# ConnectorPMOD.net
KiCad netlist of a schematic drawn in Altium Designer
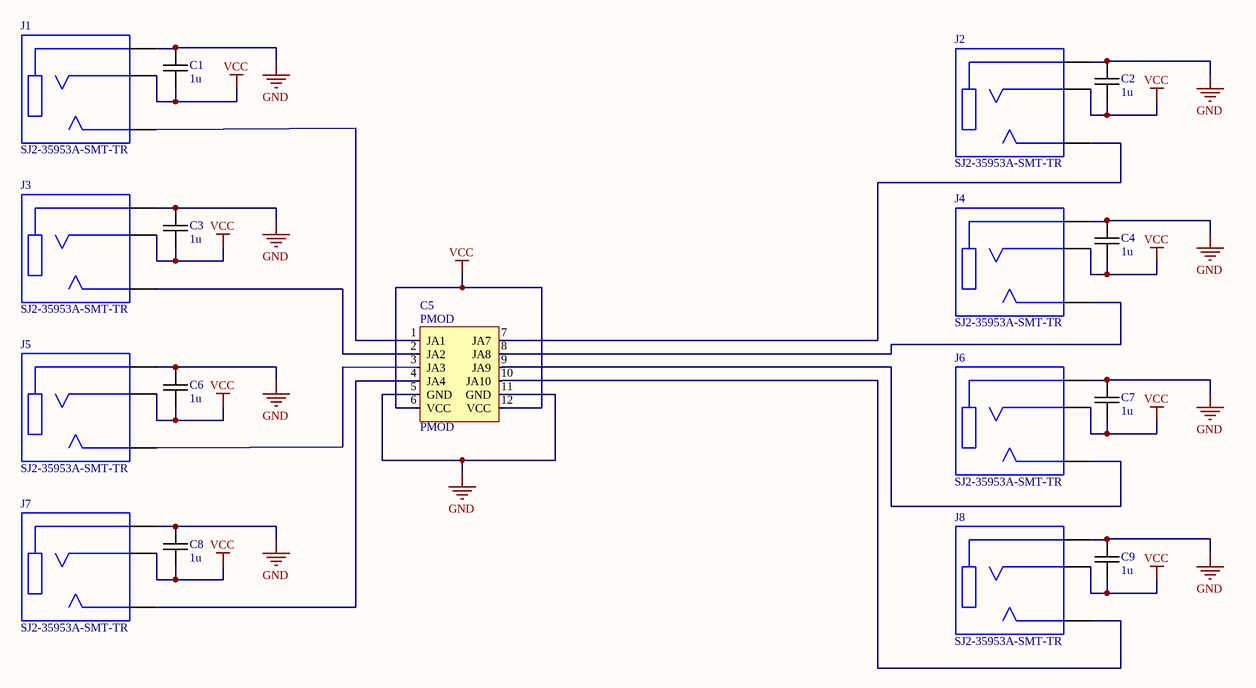
[diagram p0: ConnectorPMOD.SchDoc]

(export (version "E")
  (design (tool "Eeschema 10.0.6"))
  (components
    (comp (ref "C1")
      (value "1u")
      (footprint "0805C-GENERIC")
      (description "GENERIC CAPACITOR NON POLARISED0603")
      (libsource (lib "vh_altium_library") (part "C0805-GENERIC"))
    )
    (comp (ref "C2")
      (value "1u")
      (footprint "0805C-GENERIC")
      (description "GENERIC CAPACITOR NON POLARISED0603")
      (libsource (lib "vh_altium_library") (part "C0805-GENERIC"))
    )
    (comp (ref "C3")
      (value "1u")
      (footprint "0805C-GENERIC")
      (description "GENERIC CAPACITOR NON POLARISED0603")
      (libsource (lib "vh_altium_library") (part "C0805-GENERIC"))
    )
    (comp (ref "C4")
      (value "1u")
      (footprint "0805C-GENERIC")
      (description "GENERIC CAPACITOR NON POLARISED0603")
      (libsource (lib "vh_altium_library") (part "C0805-GENERIC"))
    )
    (comp (ref "C5") (value "PMOD") (footprint "PMOD") (libsource (lib "PMOD") (part "PMOD")))
    (comp (ref "C6")
      (value "1u")
      (footprint "0805C-GENERIC")
      (description "GENERIC CAPACITOR NON POLARISED0603")
      (libsource (lib "vh_altium_library") (part "C0805-GENERIC"))
    )
    (comp (ref "C7")
      (value "1u")
      (footprint "0805C-GENERIC")
      (description "GENERIC CAPACITOR NON POLARISED0603")
      (libsource (lib "vh_altium_library") (part "C0805-GENERIC"))
    )
    (comp (ref "C8")
      (value "1u")
      (footprint "0805C-GENERIC")
      (description "GENERIC CAPACITOR NON POLARISED0603")
      (libsource (lib "vh_altium_library") (part "C0805-GENERIC"))
    )
    (comp (ref "C9")
      (value "1u")
      (footprint "0805C-GENERIC")
      (description "GENERIC CAPACITOR NON POLARISED0603")
      (libsource (lib "vh_altium_library") (part "C0805-GENERIC"))
    )
    (comp (ref "J1")
      (value "SJ2-35953A-SMT-TR")
      (footprint "CUI_SJ2-35953A-SMT-TR")
      (description "3.5 mm, Stereo, Right Angle, Surface Mount _SMT_, Audio Jack Connector")
      (fields (field (name "MF") "CUI Devices"))
      (libsource (lib "SJ2-35953A-SMT-TR") (part "SJ2-35953A-SMT-TR"))
    )
    (comp (ref "J2")
      (value "SJ2-35953A-SMT-TR")
      (footprint "CUI_SJ2-35953A-SMT-TR")
      (description "3.5 mm, Stereo, Right Angle, Surface Mount _SMT_, Audio Jack Connector")
      (fields (field (name "MF") "CUI Devices"))
      (libsource (lib "SJ2-35953A-SMT-TR") (part "SJ2-35953A-SMT-TR"))
    )
    (comp (ref "J3")
      (value "SJ2-35953A-SMT-TR")
      (footprint "CUI_SJ2-35953A-SMT-TR")
      (description "3.5 mm, Stereo, Right Angle, Surface Mount _SMT_, Audio Jack Connector")
      (fields (field (name "MF") "CUI Devices"))
      (libsource (lib "SJ2-35953A-SMT-TR") (part "SJ2-35953A-SMT-TR"))
    )
    (comp (ref "J4")
      (value "SJ2-35953A-SMT-TR")
      (footprint "CUI_SJ2-35953A-SMT-TR")
      (description "3.5 mm, Stereo, Right Angle, Surface Mount _SMT_, Audio Jack Connector")
      (fields (field (name "MF") "CUI Devices"))
      (libsource (lib "SJ2-35953A-SMT-TR") (part "SJ2-35953A-SMT-TR"))
    )
    (comp (ref "J5")
      (value "SJ2-35953A-SMT-TR")
      (footprint "CUI_SJ2-35953A-SMT-TR")
      (description "3.5 mm, Stereo, Right Angle, Surface Mount _SMT_, Audio Jack Connector")
      (fields (field (name "MF") "CUI Devices"))
      (libsource (lib "SJ2-35953A-SMT-TR") (part "SJ2-35953A-SMT-TR"))
    )
    (comp (ref "J6")
      (value "SJ2-35953A-SMT-TR")
      (footprint "CUI_SJ2-35953A-SMT-TR")
      (description "3.5 mm, Stereo, Right Angle, Surface Mount _SMT_, Audio Jack Connector")
      (fields (field (name "MF") "CUI Devices"))
      (libsource (lib "SJ2-35953A-SMT-TR") (part "SJ2-35953A-SMT-TR"))
    )
    (comp (ref "J7")
      (value "SJ2-35953A-SMT-TR")
      (footprint "CUI_SJ2-35953A-SMT-TR")
      (description "3.5 mm, Stereo, Right Angle, Surface Mount _SMT_, Audio Jack Connector")
      (fields (field (name "MF") "CUI Devices"))
      (libsource (lib "SJ2-35953A-SMT-TR") (part "SJ2-35953A-SMT-TR"))
    )
    (comp (ref "J8")
      (value "SJ2-35953A-SMT-TR")
      (footprint "CUI_SJ2-35953A-SMT-TR")
      (description "3.5 mm, Stereo, Right Angle, Surface Mount _SMT_, Audio Jack Connector")
      (fields (field (name "MF") "CUI Devices"))
      (libsource (lib "SJ2-35953A-SMT-TR") (part "SJ2-35953A-SMT-TR"))
    )
  )
  (nets
    (net (code "1") (name "GND") (class "Default")
      (node (ref "C1") (pin "1") (pintype "passive"))
      (node (ref "C2") (pin "1") (pintype "passive"))
      (node (ref "C3") (pin "1") (pintype "passive"))
      (node (ref "C4") (pin "1") (pintype "passive"))
      (node (ref "C5") (pin "11") (pinfunction "GND_11") (pintype "power_in"))
      (node (ref "C5") (pin "5") (pinfunction "GND_5") (pintype "power_in"))
      (node (ref "C6") (pin "1") (pintype "passive"))
      (node (ref "C7") (pin "1") (pintype "passive"))
      (node (ref "C8") (pin "1") (pintype "passive"))
      (node (ref "C9") (pin "1") (pintype "passive"))
      (node (ref "J1") (pin "1") (pinfunction "SLEEVE_1") (pintype "passive"))
      (node (ref "J2") (pin "1") (pinfunction "SLEEVE_1") (pintype "passive"))
      (node (ref "J3") (pin "1") (pinfunction "SLEEVE_1") (pintype "passive"))
      (node (ref "J4") (pin "1") (pinfunction "SLEEVE_1") (pintype "passive"))
      (node (ref "J5") (pin "1") (pinfunction "SLEEVE_1") (pintype "passive"))
      (node (ref "J6") (pin "1") (pinfunction "SLEEVE_1") (pintype "passive"))
      (node (ref "J7") (pin "1") (pinfunction "SLEEVE_1") (pintype "passive"))
      (node (ref "J8") (pin "1") (pinfunction "SLEEVE_1") (pintype "passive"))
    )
    (net (code "2") (name "Net-(C5-JA1)") (class "Default")
      (node (ref "C5") (pin "1") (pinfunction "JA1_1") (pintype "output"))
      (node (ref "J1") (pin "2") (pinfunction "TIP_2") (pintype "passive"))
    )
    (net (code "3") (name "Net-(C5-JA2)") (class "Default")
      (node (ref "C5") (pin "2") (pinfunction "JA2_2") (pintype "output"))
      (node (ref "J3") (pin "2") (pinfunction "TIP_2") (pintype "passive"))
    )
    (net (code "4") (name "Net-(C5-JA3)") (class "Default")
      (node (ref "C5") (pin "3") (pinfunction "JA3_3") (pintype "output"))
      (node (ref "J5") (pin "2") (pinfunction "TIP_2") (pintype "passive"))
    )
    (net (code "5") (name "Net-(C5-JA4)") (class "Default")
      (node (ref "C5") (pin "4") (pinfunction "JA4_4") (pintype "output"))
      (node (ref "J7") (pin "2") (pinfunction "TIP_2") (pintype "passive"))
    )
    (net (code "6") (name "Net-(C5-JA7)") (class "Default")
      (node (ref "C5") (pin "7") (pinfunction "JA7_7") (pintype "output"))
      (node (ref "J2") (pin "2") (pinfunction "TIP_2") (pintype "passive"))
    )
    (net (code "7") (name "Net-(C5-JA8)") (class "Default")
      (node (ref "C5") (pin "8") (pinfunction "JA8_8") (pintype "output"))
      (node (ref "J4") (pin "2") (pinfunction "TIP_2") (pintype "passive"))
    )
    (net (code "8") (name "Net-(C5-JA9)") (class "Default")
      (node (ref "C5") (pin "9") (pinfunction "JA9_9") (pintype "output"))
      (node (ref "J6") (pin "2") (pinfunction "TIP_2") (pintype "passive"))
    )
    (net (code "9") (name "Net-(C5-JA10)") (class "Default")
      (node (ref "C5") (pin "10") (pinfunction "JA10_10") (pintype "output"))
      (node (ref "J8") (pin "2") (pinfunction "TIP_2") (pintype "passive"))
    )
    (net (code "10") (name "VCC") (class "Default")
      (node (ref "C1") (pin "2") (pintype "passive"))
      (node (ref "C2") (pin "2") (pintype "passive"))
      (node (ref "C3") (pin "2") (pintype "passive"))
      (node (ref "C4") (pin "2") (pintype "passive"))
      (node (ref "C5") (pin "12") (pinfunction "VCC_12") (pintype "power_in"))
      (node (ref "C5") (pin "6") (pinfunction "VCC_6") (pintype "power_in"))
      (node (ref "C6") (pin "2") (pintype "passive"))
      (node (ref "C7") (pin "2") (pintype "passive"))
      (node (ref "C8") (pin "2") (pintype "passive"))
      (node (ref "C9") (pin "2") (pintype "passive"))
      (node (ref "J1") (pin "3") (pinfunction "RING1_3") (pintype "passive"))
      (node (ref "J2") (pin "3") (pinfunction "RING1_3") (pintype "passive"))
      (node (ref "J3") (pin "3") (pinfunction "RING1_3") (pintype "passive"))
      (node (ref "J4") (pin "3") (pinfunction "RING1_3") (pintype "passive"))
      (node (ref "J5") (pin "3") (pinfunction "RING1_3") (pintype "passive"))
      (node (ref "J6") (pin "3") (pinfunction "RING1_3") (pintype "passive"))
      (node (ref "J7") (pin "3") (pinfunction "RING1_3") (pintype "passive"))
      (node (ref "J8") (pin "3") (pinfunction "RING1_3") (pintype "passive"))
    )
  )
)
